# amp.net
KiCad netlist of a schematic drawn in Altium Designer
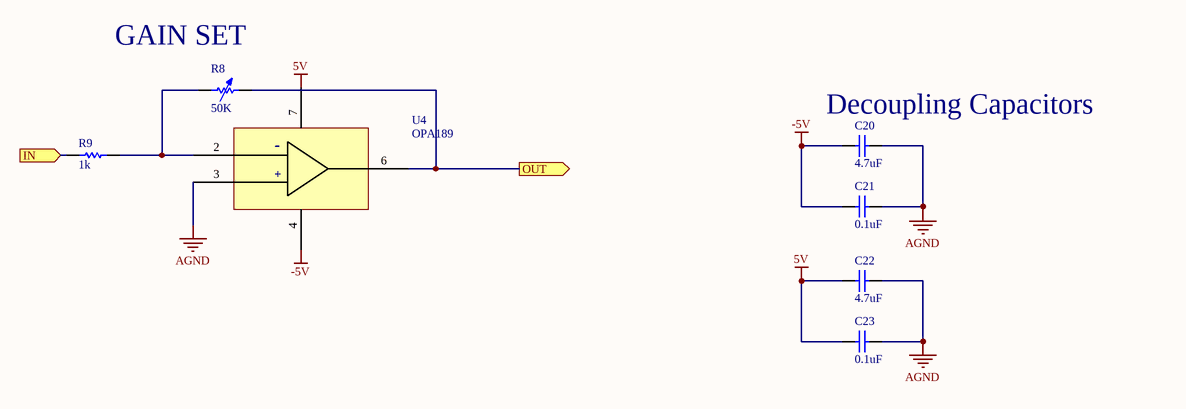
[diagram p0: amp.SchDoc]

(export (version "E")
  (design (tool "Eeschema 10.0.6"))
  (components
    (comp (ref "C20")
      (value "4.7uF")
      (footprint "0402_Cap")
      (description "Capacitor, 4.7uF, 0805")
      (libsource (lib "Arturo_Approved") (part "CL21A475KAQNNNE"))
    )
    (comp (ref "C21")
      (value "0.1uF")
      (footprint "0402_Cap")
      (description "Capacitor, 0.1uF, 0805")
      (libsource (lib "Arturo_Approved") (part "CL21B104KACNNNC"))
    )
    (comp (ref "C22")
      (value "4.7uF")
      (footprint "0402_Cap")
      (description "Capacitor, 4.7uF, 0805")
      (libsource (lib "Arturo_Approved") (part "CL21A475KAQNNNE"))
    )
    (comp (ref "C23")
      (value "0.1uF")
      (footprint "0402_Cap")
      (description "Capacitor, 0.1uF, 0805")
      (libsource (lib "Arturo_Approved") (part "CL21B104KACNNNC"))
    )
    (comp (ref "R8")
      (value "50K")
      (footprint "TRIMRES")
      (description "Variable Resistor")
      (libsource (lib "Arturo_Approved") (part "3296W-1-103LF"))
    )
    (comp (ref "R9")
      (value "1k")
      (footprint "0402_Res")
      (description "1K 1% 1/4W")
      (libsource (lib "Arturo_Approved") (part "RNCP0805FTD1K00"))
    )
    (comp (ref "U4")
      (value "OPA189")
      (footprint "SOIC_8")
      (description "Precision OpAmp, Generic")
      (libsource (lib "Arturo_Approved") (part "OPA189IDR"))
    )
  )
  (nets
    (net (code "1") (name "-5V") (class "Default")
      (node (ref "C20") (pin "1") (pinfunction "1_1") (pintype "passive"))
      (node (ref "C21") (pin "1") (pinfunction "1_1") (pintype "passive"))
      (node (ref "U4") (pin "4") (pintype "passive"))
    )
    (net (code "2") (name "/IN") (class "Default")
      (node (ref "R9") (pin "1") (pinfunction "1_1") (pintype "passive"))
    )
    (net (code "3") (name "/OUT") (class "Default")
      (node (ref "R8") (pin "2") (pinfunction "2_2") (pintype "passive"))
      (node (ref "U4") (pin "6") (pintype "passive"))
    )
    (net (code "4") (name "5V") (class "Default")
      (node (ref "C22") (pin "1") (pinfunction "1_1") (pintype "passive"))
      (node (ref "C23") (pin "1") (pinfunction "1_1") (pintype "passive"))
      (node (ref "U4") (pin "7") (pintype "passive"))
    )
    (net (code "5") (name "AGND") (class "Default")
      (node (ref "C20") (pin "2") (pinfunction "2_2") (pintype "passive"))
      (node (ref "C21") (pin "2") (pinfunction "2_2") (pintype "passive"))
      (node (ref "C22") (pin "2") (pinfunction "2_2") (pintype "passive"))
      (node (ref "C23") (pin "2") (pinfunction "2_2") (pintype "passive"))
      (node (ref "U4") (pin "3") (pintype "passive"))
    )
    (net (code "6") (name "Net-(R8-Pad1)") (class "Default")
      (node (ref "R8") (pin "1") (pinfunction "1_1") (pintype "passive"))
      (node (ref "R9") (pin "2") (pinfunction "2_2") (pintype "passive"))
      (node (ref "U4") (pin "2") (pintype "passive"))
    )
  )
)
